# SW6106_A_B_C_MCU_SEG.net
KiCad netlist of a schematic drawn in Altium Designer
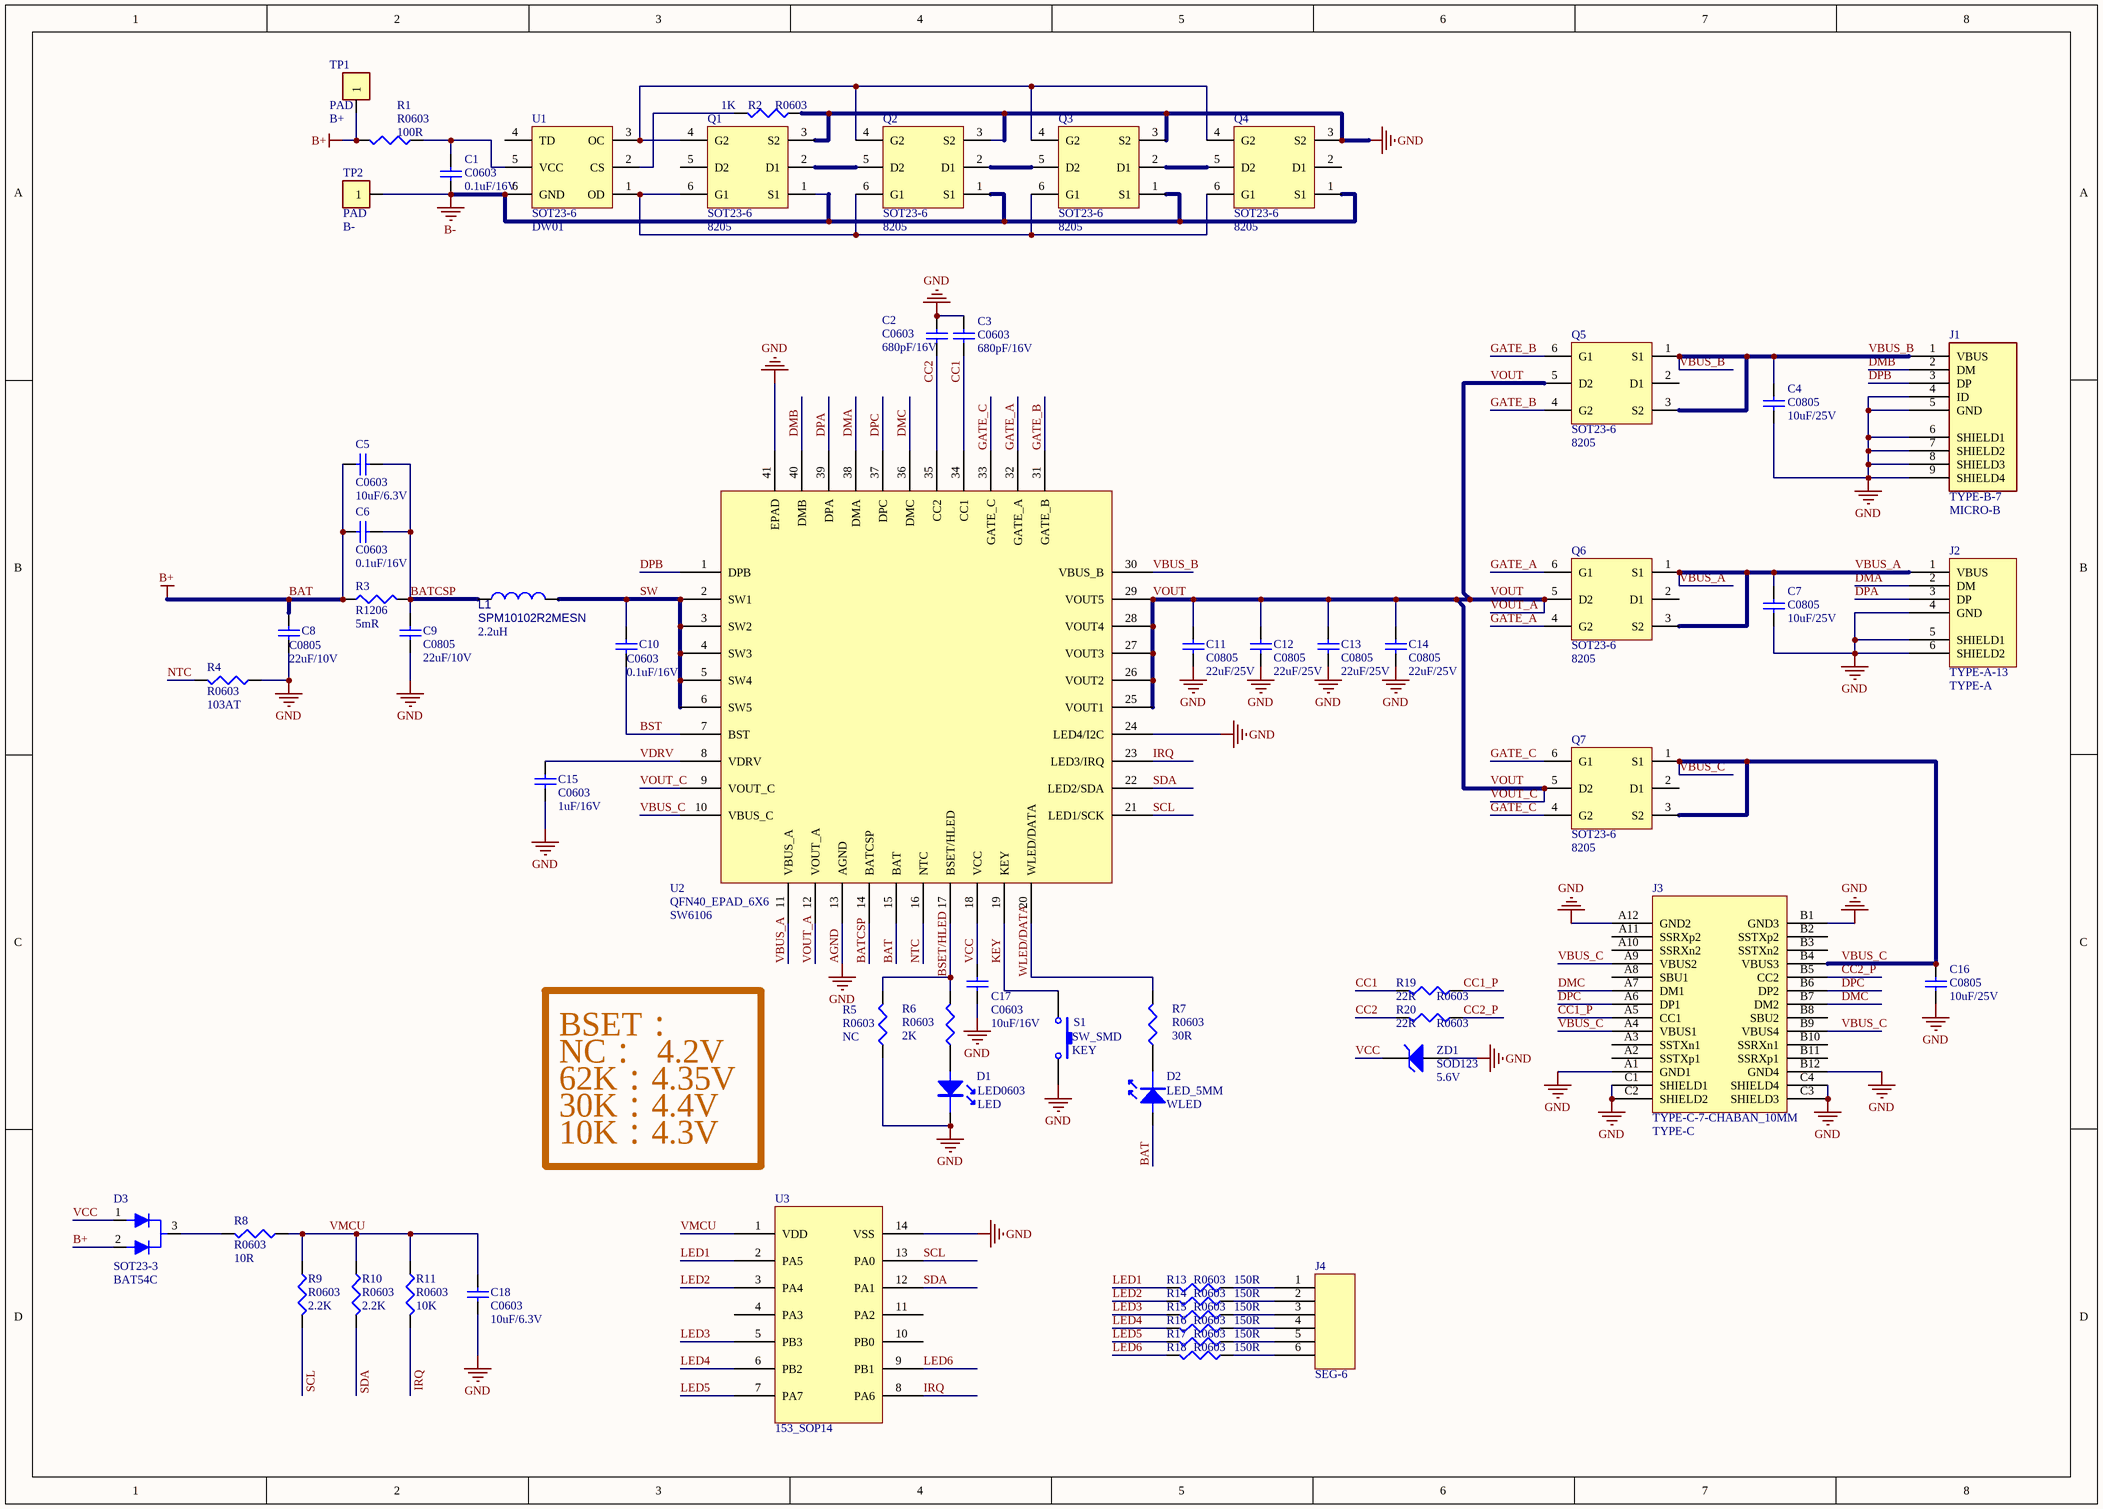
[diagram p0: SW6106+A+B+C+MCU+SEG.SchDoc]

(export (version "E")
  (design (tool "Eeschema 10.0.6"))
  (components
    (comp (ref "C1")
      (value "C0603")
      (footprint "C0603")
      (description "Capacitor")
      (fields (field (name "ALTIUM_VALUE") "0.1uF/16V") (field (name "PUBLISHER") "Altium Limited"))
      (libsource (lib "*") (part "Cap"))
    )
    (comp (ref "C2")
      (value "C0603")
      (footprint "C0603")
      (description "Capacitor")
      (fields (field (name "ALTIUM_VALUE") "680pF/16V") (field (name "PUBLISHER") "Altium Limited"))
      (libsource (lib "*") (part "CAP0603"))
    )
    (comp (ref "C3")
      (value "C0603")
      (footprint "C0603")
      (description "Capacitor")
      (fields (field (name "ALTIUM_VALUE") "680pF/16V") (field (name "PUBLISHER") "Altium Limited"))
      (libsource (lib "*") (part "CAP0603"))
    )
    (comp (ref "C4")
      (value "C0805")
      (footprint "C0805")
      (description "Capacitor")
      (fields (field (name "ALTIUM_VALUE") "10uF/25V") (field (name "PUBLISHER") "Altium Limited"))
      (libsource (lib "*") (part "CAP0603"))
    )
    (comp (ref "C5")
      (value "C0603")
      (footprint "C0603")
      (description "Capacitor")
      (fields (field (name "ALTIUM_VALUE") "10uF/6.3V") (field (name "PUBLISHER") "Altium Limited"))
      (libsource (lib "*") (part "CAP0603"))
    )
    (comp (ref "C6")
      (value "C0603")
      (footprint "C0603")
      (description "Capacitor")
      (fields (field (name "ALTIUM_VALUE") "0.1uF/16V") (field (name "PUBLISHER") "Altium Limited"))
      (libsource (lib "*") (part "CAP0603"))
    )
    (comp (ref "C7")
      (value "C0805")
      (footprint "C0805")
      (description "Capacitor")
      (fields (field (name "ALTIUM_VALUE") "10uF/25V") (field (name "PUBLISHER") "Altium Limited"))
      (libsource (lib "*") (part "CAP0603"))
    )
    (comp (ref "C8")
      (value "C0805")
      (footprint "C0805")
      (description "Capacitor")
      (fields (field (name "ALTIUM_VALUE") "22uF/10V") (field (name "PUBLISHER") "Altium Limited"))
      (libsource (lib "*") (part "CAP0805"))
    )
    (comp (ref "C9")
      (value "C0805")
      (footprint "C0805")
      (description "Capacitor")
      (fields (field (name "ALTIUM_VALUE") "22uF/10V") (field (name "PUBLISHER") "Altium Limited"))
      (libsource (lib "*") (part "CAP0805"))
    )
    (comp (ref "C10")
      (value "C0603")
      (footprint "C0603")
      (description "Capacitor")
      (fields (field (name "ALTIUM_VALUE") "0.1uF/16V") (field (name "PUBLISHER") "Altium Limited"))
      (libsource (lib "*") (part "CAP0603"))
    )
    (comp (ref "C11")
      (value "C0805")
      (footprint "C0805")
      (description "Capacitor")
      (fields (field (name "ALTIUM_VALUE") "22uF/25V") (field (name "PUBLISHER") "Altium Limited"))
      (libsource (lib "*") (part "CAP0805"))
    )
    (comp (ref "C12")
      (value "C0805")
      (footprint "C0805")
      (description "Capacitor")
      (fields (field (name "ALTIUM_VALUE") "22uF/25V") (field (name "PUBLISHER") "Altium Limited"))
      (libsource (lib "*") (part "CAP0805"))
    )
    (comp (ref "C13")
      (value "C0805")
      (footprint "C0805")
      (description "Capacitor")
      (fields (field (name "ALTIUM_VALUE") "22uF/25V") (field (name "PUBLISHER") "Altium Limited"))
      (libsource (lib "*") (part "CAP0805"))
    )
    (comp (ref "C14")
      (value "C0805")
      (footprint "C0805")
      (description "Capacitor")
      (fields (field (name "ALTIUM_VALUE") "22uF/25V") (field (name "PUBLISHER") "Altium Limited"))
      (libsource (lib "*") (part "CAP0805"))
    )
    (comp (ref "C15")
      (value "C0603")
      (footprint "C0603")
      (description "Capacitor")
      (fields (field (name "ALTIUM_VALUE") "1uF/16V") (field (name "PUBLISHER") "Altium Limited"))
      (libsource (lib "*") (part "CAP0603"))
    )
    (comp (ref "C16")
      (value "C0805")
      (footprint "C0805")
      (description "Capacitor")
      (fields (field (name "ALTIUM_VALUE") "10uF/25V") (field (name "PUBLISHER") "Altium Limited"))
      (libsource (lib "*") (part "CAP0603"))
    )
    (comp (ref "C17")
      (value "C0603")
      (footprint "C0603")
      (description "Capacitor")
      (fields (field (name "ALTIUM_VALUE") "10uF/16V") (field (name "PUBLISHER") "Altium Limited"))
      (libsource (lib "*") (part "CAP0603"))
    )
    (comp (ref "C18")
      (value "C0603")
      (footprint "C0603")
      (description "Capacitor")
      (fields (field (name "ALTIUM_VALUE") "10uF/6.3V") (field (name "PUBLISHER") "Altium Limited"))
      (libsource (lib "*") (part "CAP0603"))
    )
    (comp (ref "D1") (value "LED") (footprint "LED0603") (libsource (lib "*") (part "LED")))
    (comp (ref "D2")
      (value "WLED")
      (footprint "LED_5MM")
      (fields (field (name "FOOTPRINF") "LED_5MM") (field (name "Comment") "LED_5MM"))
      (libsource (lib "*") (part "LED"))
    )
    (comp (ref "D3") (value "BAT54C") (footprint "SOT23-3") (libsource (lib "Schlib1-2012") (part "D3")))
    (comp (ref "J1")
      (value "MICRO-B")
      (footprint "TYPE-B-7")
      (fields (field (name "FOOTPRINTF") "TYPE-B-7") (field (name "Comment") "USB_MICRO_B"))
      (libsource (lib "*") (part "USB_MICRO_B"))
    )
    (comp (ref "J2")
      (value "TYPE-A")
      (footprint "TYPE-A-13")
      (fields (field (name "FOOTPRINF") "TYPE-A-13") (field (name "Comment") "TYPE-A-1"))
      (libsource (lib "*") (part "TYPE-A-1"))
    )
    (comp (ref "J3")
      (value "TYPE-C")
      (footprint "TYPE-C-7-CHABAN_10MM")
      (libsource (lib "*") (part "TYPE-C"))
    )
    (comp (ref "J4") (value "SEG-6") (libsource (lib "TEST") (part "LCD-6")))
    (comp (ref "L1")
      (value "SPM10102R2MESN")
      (footprint "INDUCTOR_SPM1010")
      (fields (field (name "ALTIUM_VALUE") "2.2uH"))
      (libsource (lib "*") (part "INDUCTOR"))
    )
    (comp (ref "Q1")
      (value "8205")
      (footprint "SOT23-6")
      (fields (field (name "FOOTPRINF") "SOT23-6"))
      (libsource (lib "*") (part "8205B"))
    )
    (comp (ref "Q2")
      (value "8205")
      (footprint "SOT23-6")
      (fields (field (name "FOOTPRINF") "SOT23-6"))
      (libsource (lib "*") (part "8205B"))
    )
    (comp (ref "Q3")
      (value "8205")
      (footprint "SOT23-6")
      (fields (field (name "FOOTPRINF") "SOT23-6"))
      (libsource (lib "*") (part "8205B"))
    )
    (comp (ref "Q4")
      (value "8205")
      (footprint "SOT23-6")
      (fields (field (name "FOOTPRINF") "SOT23-6"))
      (libsource (lib "*") (part "8205B"))
    )
    (comp (ref "Q5")
      (value "8205")
      (footprint "SOT23-6")
      (fields (field (name "FOOTPRINF") "SOT23-6"))
      (libsource (lib "") (part "8205B_1"))
    )
    (comp (ref "Q6")
      (value "8205")
      (footprint "SOT23-6")
      (fields (field (name "FOOTPRINF") "SOT23-6"))
      (libsource (lib "") (part "8205B_1"))
    )
    (comp (ref "Q7")
      (value "8205")
      (footprint "SOT23-6")
      (fields (field (name "FOOTPRINF") "SOT23-6"))
      (libsource (lib "") (part "8205B_1"))
    )
    (comp (ref "R1")
      (value "R0603")
      (footprint "R0603")
      (description "Resistor")
      (fields (field (name "ALTIUM_VALUE") "100R") (field (name "PUBLISHER") "Altium Limited"))
      (libsource (lib "*") (part "Res3"))
    )
    (comp (ref "R2")
      (value "R0603")
      (footprint "R0603")
      (description "Resistor")
      (fields (field (name "ALTIUM_VALUE") "1K") (field (name "PUBLISHER") "Altium Limited"))
      (libsource (lib "*") (part "Res3"))
    )
    (comp (ref "R3")
      (value "R1206")
      (footprint "R1206")
      (description "Resistor")
      (fields (field (name "ALTIUM_VALUE") "5mR") (field (name "PUBLISHER") "Altium Limited"))
      (libsource (lib "*") (part "RES"))
    )
    (comp (ref "R4")
      (value "R0603")
      (footprint "R0603")
      (description "Resistor")
      (fields (field (name "ALTIUM_VALUE") "103AT") (field (name "PUBLISHER") "Altium Limited"))
      (libsource (lib "*") (part "RES"))
    )
    (comp (ref "R5")
      (value "R0603")
      (footprint "R0603")
      (description "Resistor")
      (fields (field (name "ALTIUM_VALUE") "NC") (field (name "PUBLISHER") "Altium Limited"))
      (libsource (lib "*") (part "RES"))
    )
    (comp (ref "R6")
      (value "R0603")
      (footprint "R0603")
      (description "Resistor")
      (fields (field (name "ALTIUM_VALUE") "2K") (field (name "PUBLISHER") "Altium Limited"))
      (libsource (lib "*") (part "RES"))
    )
    (comp (ref "R7")
      (value "R0603")
      (footprint "R0603")
      (description "Resistor")
      (fields (field (name "ALTIUM_VALUE") "30R") (field (name "PUBLISHER") "Altium Limited"))
      (libsource (lib "*") (part "RES"))
    )
    (comp (ref "R8")
      (value "R0603")
      (footprint "R0603")
      (description "Resistor")
      (fields (field (name "ALTIUM_VALUE") "10R") (field (name "PUBLISHER") "Altium Limited"))
      (libsource (lib "*") (part "RES"))
    )
    (comp (ref "R9")
      (value "R0603")
      (footprint "R0603")
      (description "Resistor")
      (fields (field (name "ALTIUM_VALUE") "2.2K") (field (name "PUBLISHER") "Altium Limited"))
      (libsource (lib "*") (part "RES"))
    )
    (comp (ref "R10")
      (value "R0603")
      (footprint "R0603")
      (description "Resistor")
      (fields (field (name "ALTIUM_VALUE") "2.2K") (field (name "PUBLISHER") "Altium Limited"))
      (libsource (lib "*") (part "RES"))
    )
    (comp (ref "R11")
      (value "R0603")
      (footprint "R0603")
      (description "Resistor")
      (fields (field (name "ALTIUM_VALUE") "10K") (field (name "PUBLISHER") "Altium Limited"))
      (libsource (lib "*") (part "RES"))
    )
    (comp (ref "R13")
      (value "R0603")
      (footprint "R0603")
      (description "Resistor")
      (fields (field (name "ALTIUM_VALUE") "150R") (field (name "PUBLISHER") "Altium Limited"))
      (libsource (lib "*") (part "RES"))
    )
    (comp (ref "R14")
      (value "R0603")
      (footprint "R0603")
      (description "Resistor")
      (fields (field (name "ALTIUM_VALUE") "150R") (field (name "PUBLISHER") "Altium Limited"))
      (libsource (lib "*") (part "RES"))
    )
    (comp (ref "R15")
      (value "R0603")
      (footprint "R0603")
      (description "Resistor")
      (fields (field (name "ALTIUM_VALUE") "150R") (field (name "PUBLISHER") "Altium Limited"))
      (libsource (lib "*") (part "RES"))
    )
    (comp (ref "R16")
      (value "R0603")
      (footprint "R0603")
      (description "Resistor")
      (fields (field (name "ALTIUM_VALUE") "150R") (field (name "PUBLISHER") "Altium Limited"))
      (libsource (lib "*") (part "RES"))
    )
    (comp (ref "R17")
      (value "R0603")
      (footprint "R0603")
      (description "Resistor")
      (fields (field (name "ALTIUM_VALUE") "150R") (field (name "PUBLISHER") "Altium Limited"))
      (libsource (lib "*") (part "RES"))
    )
    (comp (ref "R18")
      (value "R0603")
      (footprint "R0603")
      (description "Resistor")
      (fields (field (name "ALTIUM_VALUE") "150R") (field (name "PUBLISHER") "Altium Limited"))
      (libsource (lib "*") (part "RES"))
    )
    (comp (ref "R19")
      (value "R0603")
      (footprint "R0603")
      (description "Resistor")
      (fields (field (name "ALTIUM_VALUE") "22R") (field (name "PUBLISHER") "Altium Limited"))
      (libsource (lib "*") (part "RES"))
    )
    (comp (ref "R20")
      (value "R0603")
      (footprint "R0603")
      (description "Resistor")
      (fields (field (name "ALTIUM_VALUE") "22R") (field (name "PUBLISHER") "Altium Limited"))
      (libsource (lib "*") (part "RES"))
    )
    (comp (ref "S1")
      (value "KEY")
      (footprint "SW_SMD")
      (fields (field (name "FOOTPRINF") "SW_SMD"))
      (libsource (lib "*") (part "SW K"))
    )
    (comp (ref "TP1") (value "B+") (footprint "PAD") (libsource (lib "*") (part "Test Point")))
    (comp (ref "TP2") (value "B-") (footprint "PAD") (libsource (lib "") (part "Test Point_1")))
    (comp (ref "U1")
      (value "DW01")
      (footprint "SOT23-6")
      (fields (field (name "FOOTPRINF") "SOT23-6"))
      (libsource (lib "*") (part "DW01"))
    )
    (comp (ref "U2")
      (value "SW6106")
      (footprint "QFN40_EPAD_6X6")
      (libsource (lib "TEST") (part "SW6106_AFC"))
    )
    (comp (ref "U3") (value "153_SOP14") (libsource (lib "TEST") (part "153_SOP14")))
    (comp (ref "ZD1")
      (value "SOD123")
      (footprint "SOD-123")
      (description "Zener Diode")
      (fields (field (name "ALTIUM_UNNAMED_1") "5.6V"))
      (libsource (lib "Miscellaneous Devices") (part "D Zener"))
    )
  )
  (nets
    (net (code "1") (name "/BATCSP") (class "Default")
      (node (ref "C5") (pin "2") (pinfunction "2_2") (pintype "passive"))
      (node (ref "C6") (pin "2") (pinfunction "2_2") (pintype "passive"))
      (node (ref "C9") (pin "2") (pinfunction "2_2") (pintype "passive"))
      (node (ref "L1") (pin "1") (pinfunction "1_1") (pintype "passive"))
      (node (ref "R3") (pin "2") (pinfunction "2_2") (pintype "passive"))
      (node (ref "U2") (pin "14") (pinfunction "BATCSP_14") (pintype "passive"))
    )
    (net (code "2") (name "/BSET{slash}HLED") (class "Default")
      (node (ref "R5") (pin "2") (pinfunction "2_2") (pintype "passive"))
      (node (ref "R6") (pin "2") (pinfunction "2_2") (pintype "passive"))
      (node (ref "U2") (pin "17") (pinfunction "BSET/HLED_17") (pintype "passive"))
    )
    (net (code "3") (name "/BST") (class "Default")
      (node (ref "C10") (pin "1") (pinfunction "1_1") (pintype "passive"))
      (node (ref "U2") (pin "7") (pinfunction "BST_7") (pintype "passive"))
    )
    (net (code "4") (name "/CC1") (class "Default")
      (node (ref "C3") (pin "1") (pinfunction "1_1") (pintype "passive"))
      (node (ref "R19") (pin "2") (pinfunction "2_2") (pintype "passive"))
      (node (ref "U2") (pin "34") (pinfunction "CC1_34") (pintype "passive"))
    )
    (net (code "5") (name "/CC1_P") (class "Default")
      (node (ref "J3") (pin "A5") (pinfunction "CC1_A5") (pintype "passive"))
      (node (ref "R19") (pin "1") (pinfunction "1_1") (pintype "passive"))
    )
    (net (code "6") (name "/CC2") (class "Default")
      (node (ref "C2") (pin "1") (pinfunction "1_1") (pintype "passive"))
      (node (ref "R20") (pin "2") (pinfunction "2_2") (pintype "passive"))
      (node (ref "U2") (pin "35") (pinfunction "CC2_35") (pintype "passive"))
    )
    (net (code "7") (name "/CC2_P") (class "Default")
      (node (ref "J3") (pin "B5") (pinfunction "CC2_B5") (pintype "passive"))
      (node (ref "R20") (pin "1") (pinfunction "1_1") (pintype "passive"))
    )
    (net (code "8") (name "/DMA") (class "Default")
      (node (ref "J2") (pin "2") (pinfunction "DM_2") (pintype "passive"))
      (node (ref "U2") (pin "38") (pinfunction "DMA_38") (pintype "passive"))
    )
    (net (code "9") (name "/DMB") (class "Default")
      (node (ref "J1") (pin "2") (pinfunction "DM_2") (pintype "passive"))
      (node (ref "U2") (pin "40") (pinfunction "DMB_40") (pintype "passive"))
    )
    (net (code "10") (name "/DMC") (class "Default")
      (node (ref "J3") (pin "A7") (pinfunction "DM1_A7") (pintype "passive"))
      (node (ref "J3") (pin "B7") (pinfunction "DM2_B7") (pintype "passive"))
      (node (ref "U2") (pin "36") (pinfunction "DMC_36") (pintype "passive"))
    )
    (net (code "11") (name "/DPA") (class "Default")
      (node (ref "J2") (pin "3") (pinfunction "DP_3") (pintype "passive"))
      (node (ref "U2") (pin "39") (pinfunction "DPA_39") (pintype "passive"))
    )
    (net (code "12") (name "/DPB") (class "Default")
      (node (ref "J1") (pin "3") (pinfunction "DP_3") (pintype "passive"))
      (node (ref "U2") (pin "1") (pinfunction "DPB_1") (pintype "passive"))
    )
    (net (code "13") (name "/DPC") (class "Default")
      (node (ref "J3") (pin "A6") (pinfunction "DP1_A6") (pintype "passive"))
      (node (ref "J3") (pin "B6") (pinfunction "DP2_B6") (pintype "passive"))
      (node (ref "U2") (pin "37") (pinfunction "DPC_37") (pintype "passive"))
    )
    (net (code "14") (name "/GATE_A") (class "Default")
      (node (ref "Q6") (pin "4") (pinfunction "G2_4") (pintype "passive"))
      (node (ref "Q6") (pin "6") (pinfunction "G1_6") (pintype "passive"))
      (node (ref "U2") (pin "32") (pinfunction "GATE_A_32") (pintype "passive"))
    )
    (net (code "15") (name "/GATE_B") (class "Default")
      (node (ref "Q5") (pin "4") (pinfunction "G2_4") (pintype "passive"))
      (node (ref "Q5") (pin "6") (pinfunction "G1_6") (pintype "passive"))
      (node (ref "U2") (pin "31") (pinfunction "GATE_B_31") (pintype "passive"))
    )
    (net (code "16") (name "/GATE_C") (class "Default")
      (node (ref "Q7") (pin "4") (pinfunction "G2_4") (pintype "passive"))
      (node (ref "Q7") (pin "6") (pinfunction "G1_6") (pintype "passive"))
      (node (ref "U2") (pin "33") (pinfunction "GATE_C_33") (pintype "passive"))
    )
    (net (code "17") (name "/IRQ") (class "Default")
      (node (ref "R11") (pin "2") (pinfunction "2_2") (pintype "passive"))
      (node (ref "U2") (pin "23") (pinfunction "LED3/IRQ_23") (pintype "passive"))
      (node (ref "U3") (pin "8") (pinfunction "PA6_8") (pintype "passive"))
    )
    (net (code "18") (name "/KEY") (class "Default")
      (node (ref "S1") (pin "1") (pinfunction "1_1") (pintype "passive"))
      (node (ref "U2") (pin "19") (pinfunction "KEY_19") (pintype "passive"))
    )
    (net (code "19") (name "/LED1") (class "Default")
      (node (ref "R13") (pin "2") (pinfunction "2_2") (pintype "passive"))
      (node (ref "U3") (pin "2") (pinfunction "PA5_2") (pintype "passive"))
    )
    (net (code "20") (name "/LED2") (class "Default")
      (node (ref "R14") (pin "2") (pinfunction "2_2") (pintype "passive"))
      (node (ref "U3") (pin "3") (pinfunction "PA4_3") (pintype "passive"))
    )
    (net (code "21") (name "/LED3") (class "Default")
      (node (ref "R15") (pin "2") (pinfunction "2_2") (pintype "passive"))
      (node (ref "U3") (pin "5") (pinfunction "PB3_5") (pintype "passive"))
    )
    (net (code "22") (name "/LED4") (class "Default")
      (node (ref "R16") (pin "2") (pinfunction "2_2") (pintype "passive"))
      (node (ref "U3") (pin "6") (pinfunction "PB2_6") (pintype "passive"))
    )
    (net (code "23") (name "/LED5") (class "Default")
      (node (ref "R17") (pin "2") (pinfunction "2_2") (pintype "passive"))
      (node (ref "U3") (pin "7") (pinfunction "PA7_7") (pintype "passive"))
    )
    (net (code "24") (name "/LED6") (class "Default")
      (node (ref "R18") (pin "2") (pinfunction "2_2") (pintype "passive"))
      (node (ref "U3") (pin "9") (pinfunction "PB1_9") (pintype "passive"))
    )
    (net (code "25") (name "/NTC") (class "Default")
      (node (ref "R4") (pin "2") (pinfunction "2_2") (pintype "passive"))
      (node (ref "U2") (pin "16") (pinfunction "NTC_16") (pintype "passive"))
    )
    (net (code "26") (name "/SCL") (class "Default")
      (node (ref "R9") (pin "2") (pinfunction "2_2") (pintype "passive"))
      (node (ref "U2") (pin "21") (pinfunction "LED1/SCK_21") (pintype "passive"))
      (node (ref "U3") (pin "13") (pinfunction "PA0_13") (pintype "passive"))
    )
    (net (code "27") (name "/SDA") (class "Default")
      (node (ref "R10") (pin "2") (pinfunction "2_2") (pintype "passive"))
      (node (ref "U2") (pin "22") (pinfunction "LED2/SDA_22") (pintype "passive"))
      (node (ref "U3") (pin "12") (pinfunction "PA1_12") (pintype "passive"))
    )
    (net (code "28") (name "/SW") (class "Default")
      (node (ref "C10") (pin "2") (pinfunction "2_2") (pintype "passive"))
      (node (ref "L1") (pin "2") (pinfunction "2_2") (pintype "passive"))
      (node (ref "U2") (pin "2") (pinfunction "SW1_2") (pintype "passive"))
      (node (ref "U2") (pin "3") (pinfunction "SW2_3") (pintype "passive"))
      (node (ref "U2") (pin "4") (pinfunction "SW3_4") (pintype "passive"))
      (node (ref "U2") (pin "5") (pinfunction "SW4_5") (pintype "passive"))
      (node (ref "U2") (pin "6") (pinfunction "SW5_6") (pintype "passive"))
    )
    (net (code "29") (name "/VBUS_A") (class "Default")
      (node (ref "C7") (pin "2") (pinfunction "2_2") (pintype "passive"))
      (node (ref "J2") (pin "1") (pinfunction "VBUS_1") (pintype "passive"))
      (node (ref "Q6") (pin "1") (pinfunction "S1_1") (pintype "passive"))
      (node (ref "Q6") (pin "3") (pinfunction "S2_3") (pintype "passive"))
      (node (ref "U2") (pin "11") (pinfunction "VBUS_A_11") (pintype "passive"))
    )
    (net (code "30") (name "/VBUS_B") (class "Default")
      (node (ref "C4") (pin "2") (pinfunction "2_2") (pintype "passive"))
      (node (ref "J1") (pin "1") (pinfunction "VBUS_1") (pintype "passive"))
      (node (ref "Q5") (pin "1") (pinfunction "S1_1") (pintype "passive"))
      (node (ref "Q5") (pin "3") (pinfunction "S2_3") (pintype "passive"))
      (node (ref "U2") (pin "30") (pinfunction "VBUS_B_30") (pintype "passive"))
    )
    (net (code "31") (name "/VBUS_C") (class "Default")
      (node (ref "C16") (pin "2") (pinfunction "2_2") (pintype "passive"))
      (node (ref "J3") (pin "A4") (pinfunction "VBUS1_A4") (pintype "passive"))
      (node (ref "J3") (pin "A9") (pinfunction "VBUS2_A9") (pintype "passive"))
      (node (ref "J3") (pin "B4") (pinfunction "VBUS3_B4") (pintype "passive"))
      (node (ref "J3") (pin "B9") (pinfunction "VBUS4_B9") (pintype "passive"))
      (node (ref "Q7") (pin "1") (pinfunction "S1_1") (pintype "passive"))
      (node (ref "Q7") (pin "3") (pinfunction "S2_3") (pintype "passive"))
      (node (ref "U2") (pin "10") (pinfunction "VBUS_C_10") (pintype "passive"))
    )
    (net (code "32") (name "/VCC") (class "Default")
      (node (ref "C17") (pin "2") (pinfunction "2_2") (pintype "passive"))
      (node (ref "D3") (pin "1") (pintype "passive"))
      (node (ref "U2") (pin "18") (pinfunction "VCC_18") (pintype "passive"))
      (node (ref "ZD1") (pin "2") (pinfunction "K_2") (pintype "passive"))
    )
    (net (code "33") (name "/VDRV") (class "Default")
      (node (ref "C15") (pin "2") (pinfunction "2_2") (pintype "passive"))
      (node (ref "U2") (pin "8") (pinfunction "VDRV_8") (pintype "passive"))
    )
    (net (code "34") (name "/VMCU") (class "Default")
      (node (ref "C18") (pin "1") (pinfunction "1_1") (pintype "passive"))
      (node (ref "R10") (pin "1") (pinfunction "1_1") (pintype "passive"))
      (node (ref "R11") (pin "1") (pinfunction "1_1") (pintype "passive"))
      (node (ref "R8") (pin "1") (pinfunction "1_1") (pintype "passive"))
      (node (ref "R9") (pin "1") (pinfunction "1_1") (pintype "passive"))
      (node (ref "U3") (pin "1") (pinfunction "VDD_1") (pintype "passive"))
    )
    (net (code "35") (name "/VOUT") (class "Default")
      (node (ref "C11") (pin "2") (pinfunction "2_2") (pintype "passive"))
      (node (ref "C12") (pin "2") (pinfunction "2_2") (pintype "passive"))
      (node (ref "C13") (pin "2") (pinfunction "2_2") (pintype "passive"))
      (node (ref "C14") (pin "2") (pinfunction "2_2") (pintype "passive"))
      (node (ref "Q5") (pin "5") (pinfunction "D2_5") (pintype "passive"))
      (node (ref "Q6") (pin "5") (pinfunction "D2_5") (pintype "passive"))
      (node (ref "Q7") (pin "5") (pinfunction "D2_5") (pintype "passive"))
      (node (ref "U2") (pin "12") (pinfunction "VOUT_A_12") (pintype "passive"))
      (node (ref "U2") (pin "25") (pinfunction "VOUT1_25") (pintype "passive"))
      (node (ref "U2") (pin "26") (pinfunction "VOUT2_26") (pintype "passive"))
      (node (ref "U2") (pin "27") (pinfunction "VOUT3_27") (pintype "passive"))
      (node (ref "U2") (pin "28") (pinfunction "VOUT4_28") (pintype "passive"))
      (node (ref "U2") (pin "29") (pinfunction "VOUT5_29") (pintype "passive"))
      (node (ref "U2") (pin "9") (pinfunction "VOUT_C_9") (pintype "passive"))
    )
    (net (code "36") (name "/WLED{slash}DATA") (class "Default")
      (node (ref "R7") (pin "2") (pinfunction "2_2") (pintype "passive"))
      (node (ref "U2") (pin "20") (pinfunction "WLED/DATA_20") (pintype "passive"))
    )
    (net (code "37") (name "B+") (class "Default")
      (node (ref "C5") (pin "1") (pinfunction "1_1") (pintype "passive"))
      (node (ref "C6") (pin "1") (pinfunction "1_1") (pintype "passive"))
      (node (ref "C8") (pin "2") (pinfunction "2_2") (pintype "passive"))
      (node (ref "D2") (pin "1") (pinfunction "A_1") (pintype "passive"))
      (node (ref "D3") (pin "2") (pintype "passive"))
      (node (ref "R1") (pin "2") (pinfunction "2_2") (pintype "passive"))
      (node (ref "R3") (pin "1") (pinfunction "1_1") (pintype "passive"))
      (node (ref "TP1") (pin "1") (pinfunction "1_1") (pintype "passive"))
      (node (ref "U2") (pin "15") (pinfunction "BAT_15") (pintype "passive"))
    )
    (net (code "38") (name "B-") (class "Default")
      (node (ref "C1") (pin "1") (pinfunction "1_1") (pintype "passive"))
      (node (ref "Q1") (pin "1") (pinfunction "S1_1") (pintype "passive"))
      (node (ref "Q2") (pin "1") (pinfunction "S1_1") (pintype "passive"))
      (node (ref "Q3") (pin "1") (pinfunction "S1_1") (pintype "passive"))
      (node (ref "Q4") (pin "1") (pinfunction "S1_1") (pintype "passive"))
      (node (ref "TP2") (pin "1") (pinfunction "1_1") (pintype "passive"))
      (node (ref "U1") (pin "6") (pinfunction "GND_6") (pintype "passive"))
    )
    (net (code "39") (name "GND") (class "Default")
      (node (ref "C11") (pin "1") (pinfunction "1_1") (pintype "passive"))
      (node (ref "C12") (pin "1") (pinfunction "1_1") (pintype "passive"))
      (node (ref "C13") (pin "1") (pinfunction "1_1") (pintype "passive"))
      (node (ref "C14") (pin "1") (pinfunction "1_1") (pintype "passive"))
      (node (ref "C15") (pin "1") (pinfunction "1_1") (pintype "passive"))
      (node (ref "C16") (pin "1") (pinfunction "1_1") (pintype "passive"))
      (node (ref "C17") (pin "1") (pinfunction "1_1") (pintype "passive"))
      (node (ref "C18") (pin "2") (pinfunction "2_2") (pintype "passive"))
      (node (ref "C2") (pin "2") (pinfunction "2_2") (pintype "passive"))
      (node (ref "C3") (pin "2") (pinfunction "2_2") (pintype "passive"))
      (node (ref "C4") (pin "1") (pinfunction "1_1") (pintype "passive"))
      (node (ref "C7") (pin "1") (pinfunction "1_1") (pintype "passive"))
      (node (ref "C8") (pin "1") (pinfunction "1_1") (pintype "passive"))
      (node (ref "C9") (pin "1") (pinfunction "1_1") (pintype "passive"))
      (node (ref "D1") (pin "2") (pinfunction "K_2") (pintype "passive"))
      (node (ref "J1") (pin "4") (pinfunction "ID_4") (pintype "passive"))
      (node (ref "J1") (pin "5") (pinfunction "GND_5") (pintype "passive"))
      (node (ref "J1") (pin "6") (pinfunction "SHIELD1_6") (pintype "passive"))
      (node (ref "J1") (pin "7") (pinfunction "SHIELD2_7") (pintype "passive"))
      (node (ref "J1") (pin "8") (pinfunction "SHIELD3_8") (pintype "passive"))
      (node (ref "J1") (pin "9") (pinfunction "SHIELD4_9") (pintype "passive"))
      (node (ref "J2") (pin "4") (pinfunction "GND_4") (pintype "passive"))
      (node (ref "J2") (pin "5") (pinfunction "SHIELD1_5") (pintype "passive"))
      (node (ref "J2") (pin "6") (pinfunction "SHIELD2_6") (pintype "passive"))
      (node (ref "J3") (pin "A1") (pinfunction "GND1_A1") (pintype "passive"))
      (node (ref "J3") (pin "A12") (pinfunction "GND2_A12") (pintype "passive"))
      (node (ref "J3") (pin "B1") (pinfunction "GND3_B1") (pintype "passive"))
      (node (ref "J3") (pin "B12") (pinfunction "GND4_B12") (pintype "passive"))
      (node (ref "J3") (pin "C1") (pinfunction "SHIELD1_C1") (pintype "passive"))
      (node (ref "J3") (pin "C2") (pinfunction "SHIELD2_C2") (pintype "passive"))
      (node (ref "J3") (pin "C3") (pinfunction "SHIELD3_C3") (pintype "passive"))
      (node (ref "J3") (pin "C4") (pinfunction "SHIELD4_C4") (pintype "passive"))
      (node (ref "Q1") (pin "3") (pinfunction "S2_3") (pintype "passive"))
      (node (ref "Q2") (pin "3") (pinfunction "S2_3") (pintype "passive"))
      (node (ref "Q3") (pin "3") (pinfunction "S2_3") (pintype "passive"))
      (node (ref "Q4") (pin "3") (pinfunction "S2_3") (pintype "passive"))
      (node (ref "R2") (pin "1") (pinfunction "1_1") (pintype "passive"))
      (node (ref "R4") (pin "1") (pinfunction "1_1") (pintype "passive"))
      (node (ref "R5") (pin "1") (pinfunction "1_1") (pintype "passive"))
      (node (ref "S1") (pin "2") (pinfunction "2_2") (pintype "passive"))
      (node (ref "U2") (pin "13") (pinfunction "AGND_13") (pintype "passive"))
      (node (ref "U2") (pin "24") (pinfunction "LED4/I2C_24") (pintype "passive"))
      (node (ref "U2") (pin "41") (pinfunction "EPAD_41") (pintype "passive"))
      (node (ref "U3") (pin "14") (pinfunction "VSS_14") (pintype "passive"))
      (node (ref "ZD1") (pin "1") (pinfunction "A_1") (pintype "passive"))
    )
    (net (code "40") (name "Net-(D1-A)") (class "Default")
      (node (ref "D1") (pin "1") (pinfunction "A_1") (pintype "passive"))
      (node (ref "R6") (pin "1") (pinfunction "1_1") (pintype "passive"))
    )
    (net (code "41") (name "Net-(D2-K)") (class "Default")
      (node (ref "D2") (pin "2") (pinfunction "K_2") (pintype "passive"))
      (node (ref "R7") (pin "1") (pinfunction "1_1") (pintype "passive"))
    )
    (net (code "42") (name "Net-(D3-Pad3)") (class "Default")
      (node (ref "D3") (pin "3") (pintype "passive"))
      (node (ref "R8") (pin "2") (pinfunction "2_2") (pintype "passive"))
    )
    (net (code "43") (name "Net-(J4-Pad1)") (class "Default")
      (node (ref "J4") (pin "1") (pinfunction "1_1") (pintype "passive"))
      (node (ref "R13") (pin "1") (pinfunction "1_1") (pintype "passive"))
    )
    (net (code "44") (name "Net-(J4-Pad2)") (class "Default")
      (node (ref "J4") (pin "2") (pinfunction "2_2") (pintype "passive"))
      (node (ref "R14") (pin "1") (pinfunction "1_1") (pintype "passive"))
    )
    (net (code "45") (name "Net-(J4-Pad3)") (class "Default")
      (node (ref "J4") (pin "3") (pinfunction "3_3") (pintype "passive"))
      (node (ref "R15") (pin "1") (pinfunction "1_1") (pintype "passive"))
    )
    (net (code "46") (name "Net-(J4-Pad4)") (class "Default")
      (node (ref "J4") (pin "4") (pinfunction "4_4") (pintype "passive"))
      (node (ref "R16") (pin "1") (pinfunction "1_1") (pintype "passive"))
    )
    (net (code "47") (name "Net-(J4-Pad5)") (class "Default")
      (node (ref "J4") (pin "5") (pinfunction "5_5") (pintype "passive"))
      (node (ref "R17") (pin "1") (pinfunction "1_1") (pintype "passive"))
    )
    (net (code "48") (name "Net-(J4-Pad6)") (class "Default")
      (node (ref "J4") (pin "6") (pinfunction "6_6") (pintype "passive"))
      (node (ref "R18") (pin "1") (pinfunction "1_1") (pintype "passive"))
    )
    (net (code "49") (name "Net-(Q1-D1)") (class "Default")
      (node (ref "Q1") (pin "2") (pinfunction "D1_2") (pintype "passive"))
      (node (ref "Q2") (pin "5") (pinfunction "D2_5") (pintype "passive"))
    )
    (net (code "50") (name "Net-(Q1-G1)") (class "Default")
      (node (ref "Q1") (pin "6") (pinfunction "G1_6") (pintype "passive"))
      (node (ref "Q2") (pin "6") (pinfunction "G1_6") (pintype "passive"))
      (node (ref "Q3") (pin "6") (pinfunction "G1_6") (pintype "passive"))
      (node (ref "Q4") (pin "6") (pinfunction "G1_6") (pintype "passive"))
      (node (ref "U1") (pin "1") (pinfunction "OD_1") (pintype "passive"))
    )
    (net (code "51") (name "Net-(Q1-G2)") (class "Default")
      (node (ref "Q1") (pin "4") (pinfunction "G2_4") (pintype "passive"))
      (node (ref "Q2") (pin "4") (pinfunction "G2_4") (pintype "passive"))
      (node (ref "Q3") (pin "4") (pinfunction "G2_4") (pintype "passive"))
      (node (ref "Q4") (pin "4") (pinfunction "G2_4") (pintype "passive"))
      (node (ref "U1") (pin "3") (pinfunction "OC_3") (pintype "passive"))
    )
    (net (code "52") (name "Net-(Q2-D1)") (class "Default")
      (node (ref "Q2") (pin "2") (pinfunction "D1_2") (pintype "passive"))
      (node (ref "Q3") (pin "5") (pinfunction "D2_5") (pintype "passive"))
    )
    (net (code "53") (name "Net-(Q3-D1)") (class "Default")
      (node (ref "Q3") (pin "2") (pinfunction "D1_2") (pintype "passive"))
      (node (ref "Q4") (pin "5") (pinfunction "D2_5") (pintype "passive"))
    )
    (net (code "54") (name "Net-(U1-CS)") (class "Default")
      (node (ref "R2") (pin "2") (pinfunction "2_2") (pintype "passive"))
      (node (ref "U1") (pin "2") (pinfunction "CS_2") (pintype "passive"))
    )
    (net (code "55") (name "Net-(U1-VCC)") (class "Default")
      (node (ref "C1") (pin "2") (pinfunction "2_2") (pintype "passive"))
      (node (ref "R1") (pin "1") (pinfunction "1_1") (pintype "passive"))
      (node (ref "U1") (pin "5") (pinfunction "VCC_5") (pintype "passive"))
    )
    (net (code "56") (name "unconnected-(J3-SBU1-PadA8)") (class "Default")
      (node (ref "J3") (pin "A8") (pinfunction "SBU1_A8") (pintype "passive"))
    )
    (net (code "57") (name "unconnected-(J3-SBU2-PadB8)") (class "Default")
      (node (ref "J3") (pin "B8") (pinfunction "SBU2_B8") (pintype "passive"))
    )
    (net (code "58") (name "unconnected-(J3-SSRXn1-PadB10)") (class "Default")
      (node (ref "J3") (pin "B10") (pinfunction "SSRXn1_B10") (pintype "passive"))
    )
    (net (code "59") (name "unconnected-(J3-SSRXn2-PadA10)") (class "Default")
      (node (ref "J3") (pin "A10") (pinfunction "SSRXn2_A10") (pintype "passive"))
    )
    (net (code "60") (name "unconnected-(J3-SSRXp1-PadB11)") (class "Default")
      (node (ref "J3") (pin "B11") (pinfunction "SSRXp1_B11") (pintype "passive"))
    )
    (net (code "61") (name "unconnected-(J3-SSRXp2-PadA11)") (class "Default")
      (node (ref "J3") (pin "A11") (pinfunction "SSRXp2_A11") (pintype "passive"))
    )
    (net (code "62") (name "unconnected-(J3-SSTXn1-PadA3)") (class "Default")
      (node (ref "J3") (pin "A3") (pinfunction "SSTXn1_A3") (pintype "passive"))
    )
    (net (code "63") (name "unconnected-(J3-SSTXn2-PadB3)") (class "Default")
      (node (ref "J3") (pin "B3") (pinfunction "SSTXn2_B3") (pintype "passive"))
    )
    (net (code "64") (name "unconnected-(J3-SSTXp1-PadA2)") (class "Default")
      (node (ref "J3") (pin "A2") (pinfunction "SSTXp1_A2") (pintype "passive"))
    )
    (net (code "65") (name "unconnected-(J3-SSTXp2-PadB2)") (class "Default")
      (node (ref "J3") (pin "B2") (pinfunction "SSTXp2_B2") (pintype "passive"))
    )
    (net (code "66") (name "unconnected-(Q1-D2-Pad5)") (class "Default")
      (node (ref "Q1") (pin "5") (pinfunction "D2_5") (pintype "passive"))
    )
    (net (code "67") (name "unconnected-(Q4-D1-Pad2)") (class "Default")
      (node (ref "Q4") (pin "2") (pinfunction "D1_2") (pintype "passive"))
    )
    (net (code "68") (name "unconnected-(Q5-D1-Pad2)") (class "Default")
      (node (ref "Q5") (pin "2") (pinfunction "D1_2") (pintype "passive"))
    )
    (net (code "69") (name "unconnected-(Q6-D1-Pad2)") (class "Default")
      (node (ref "Q6") (pin "2") (pinfunction "D1_2") (pintype "passive"))
    )
    (net (code "70") (name "unconnected-(Q7-D1-Pad2)") (class "Default")
      (node (ref "Q7") (pin "2") (pinfunction "D1_2") (pintype "passive"))
    )
    (net (code "71") (name "unconnected-(U1-TD-Pad4)") (class "Default")
      (node (ref "U1") (pin "4") (pinfunction "TD_4") (pintype "passive"))
    )
    (net (code "72") (name "unconnected-(U3-PA2-Pad11)") (class "Default")
      (node (ref "U3") (pin "11") (pinfunction "PA2_11") (pintype "passive"))
    )
    (net (code "73") (name "unconnected-(U3-PA3-Pad4)") (class "Default")
      (node (ref "U3") (pin "4") (pinfunction "PA3_4") (pintype "passive"))
    )
    (net (code "74") (name "unconnected-(U3-PB0-Pad10)") (class "Default")
      (node (ref "U3") (pin "10") (pinfunction "PB0_10") (pintype "passive"))
    )
  )
)
